# CC-16-2_ADIS16209_Breakout_Board.net
KiCad netlist of a schematic drawn in EAGLE
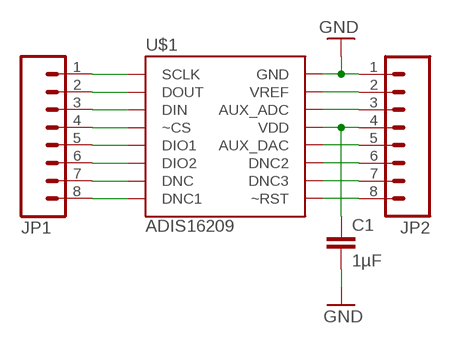
[diagram p0: schematic, sheet 1]

(export (version "E")
  (design (tool "Eeschema 10.0.6"))
  (components
    (comp (ref "C1")
      (value "1µF")
      (footprint "eagle-import:0805")
      (libsource (lib "eagle-import") (part "CAP0805"))
    )
    (comp (ref "JP1")
      (value "M08")
      (footprint "eagle-import:1X08")
      (libsource (lib "eagle-import") (part "M08"))
    )
    (comp (ref "JP2")
      (value "M08")
      (footprint "eagle-import:1X08")
      (libsource (lib "eagle-import") (part "M08"))
    )
    (comp (ref "U$1")
      (value "ADIS16209")
      (footprint "eagle-import:CC-16-2")
      (libsource (lib "eagle-import") (part "ADIS16209"))
    )
  )
  (nets
    (net (code "1") (name "GND") (class "Default")
      (node (ref "C1") (pin "2") (pinfunction "2_2") (pintype "passive"))
      (node (ref "JP2") (pin "1") (pinfunction "1_1") (pintype "passive"))
      (node (ref "U$1") (pin "P$16") (pinfunction "GND_P$16") (pintype "bidirectional"))
    )
    (net (code "2") (name "Net-(U$1-AUX_ADC)") (class "Default")
      (node (ref "JP2") (pin "3") (pinfunction "3_3") (pintype "passive"))
      (node (ref "U$1") (pin "P$14") (pinfunction "AUX_ADC_P$14") (pintype "bidirectional"))
    )
    (net (code "3") (name "Net-(U$1-AUX_DAC)") (class "Default")
      (node (ref "JP2") (pin "5") (pinfunction "5_5") (pintype "passive"))
      (node (ref "U$1") (pin "P$12") (pinfunction "AUX_DAC_P$12") (pintype "bidirectional"))
    )
    (net (code "4") (name "Net-(U$1-DIN)") (class "Default")
      (node (ref "JP1") (pin "3") (pinfunction "3_3") (pintype "passive"))
      (node (ref "U$1") (pin "P$3") (pinfunction "DIN_P$3") (pintype "bidirectional"))
    )
    (net (code "5") (name "Net-(U$1-DIO1)") (class "Default")
      (node (ref "JP1") (pin "5") (pinfunction "5_5") (pintype "passive"))
      (node (ref "U$1") (pin "P$5") (pinfunction "DIO1_P$5") (pintype "bidirectional"))
    )
    (net (code "6") (name "Net-(U$1-DIO2)") (class "Default")
      (node (ref "JP1") (pin "6") (pinfunction "6_6") (pintype "passive"))
      (node (ref "U$1") (pin "P$6") (pinfunction "DIO2_P$6") (pintype "bidirectional"))
    )
    (net (code "7") (name "Net-(U$1-DNC)") (class "Default")
      (node (ref "JP1") (pin "7") (pinfunction "7_7") (pintype "passive"))
      (node (ref "U$1") (pin "P$7") (pinfunction "DNC_P$7") (pintype "bidirectional"))
    )
    (net (code "8") (name "Net-(U$1-DNC1)") (class "Default")
      (node (ref "JP1") (pin "8") (pinfunction "8_8") (pintype "passive"))
      (node (ref "U$1") (pin "P$8") (pinfunction "DNC1_P$8") (pintype "bidirectional"))
    )
    (net (code "9") (name "Net-(U$1-DNC2)") (class "Default")
      (node (ref "JP2") (pin "6") (pinfunction "6_6") (pintype "passive"))
      (node (ref "U$1") (pin "P$11") (pinfunction "DNC2_P$11") (pintype "bidirectional"))
    )
    (net (code "10") (name "Net-(U$1-DNC3)") (class "Default")
      (node (ref "JP2") (pin "7") (pinfunction "7_7") (pintype "passive"))
      (node (ref "U$1") (pin "P$10") (pinfunction "DNC3_P$10") (pintype "bidirectional"))
    )
    (net (code "11") (name "Net-(U$1-DOUT)") (class "Default")
      (node (ref "JP1") (pin "2") (pinfunction "2_2") (pintype "passive"))
      (node (ref "U$1") (pin "P$2") (pinfunction "DOUT_P$2") (pintype "bidirectional"))
    )
    (net (code "12") (name "Net-(U$1-SCLK)") (class "Default")
      (node (ref "JP1") (pin "1") (pinfunction "1_1") (pintype "passive"))
      (node (ref "U$1") (pin "P$1") (pinfunction "SCLK_P$1") (pintype "bidirectional"))
    )
    (net (code "13") (name "Net-(U$1-VDD)") (class "Default")
      (node (ref "C1") (pin "1") (pinfunction "1_1") (pintype "passive"))
      (node (ref "JP2") (pin "4") (pinfunction "4_4") (pintype "passive"))
      (node (ref "U$1") (pin "P$13") (pinfunction "VDD_P$13") (pintype "bidirectional"))
    )
    (net (code "14") (name "Net-(U$1-VREF)") (class "Default")
      (node (ref "JP2") (pin "2") (pinfunction "2_2") (pintype "passive"))
      (node (ref "U$1") (pin "P$15") (pinfunction "VREF_P$15") (pintype "bidirectional"))
    )
    (net (code "15") (name "Net-(U$1-~{CS})") (class "Default")
      (node (ref "JP1") (pin "4") (pinfunction "4_4") (pintype "passive"))
      (node (ref "U$1") (pin "P$4") (pinfunction "~{CS}_P$4") (pintype "bidirectional"))
    )
    (net (code "16") (name "Net-(U$1-~{RST})") (class "Default")
      (node (ref "JP2") (pin "8") (pinfunction "8_8") (pintype "passive"))
      (node (ref "U$1") (pin "P$9") (pinfunction "~{RST}_P$9") (pintype "bidirectional"))
    )
  )
)
